# Voeding.net
KiCad netlist of a schematic drawn in Altium Designer
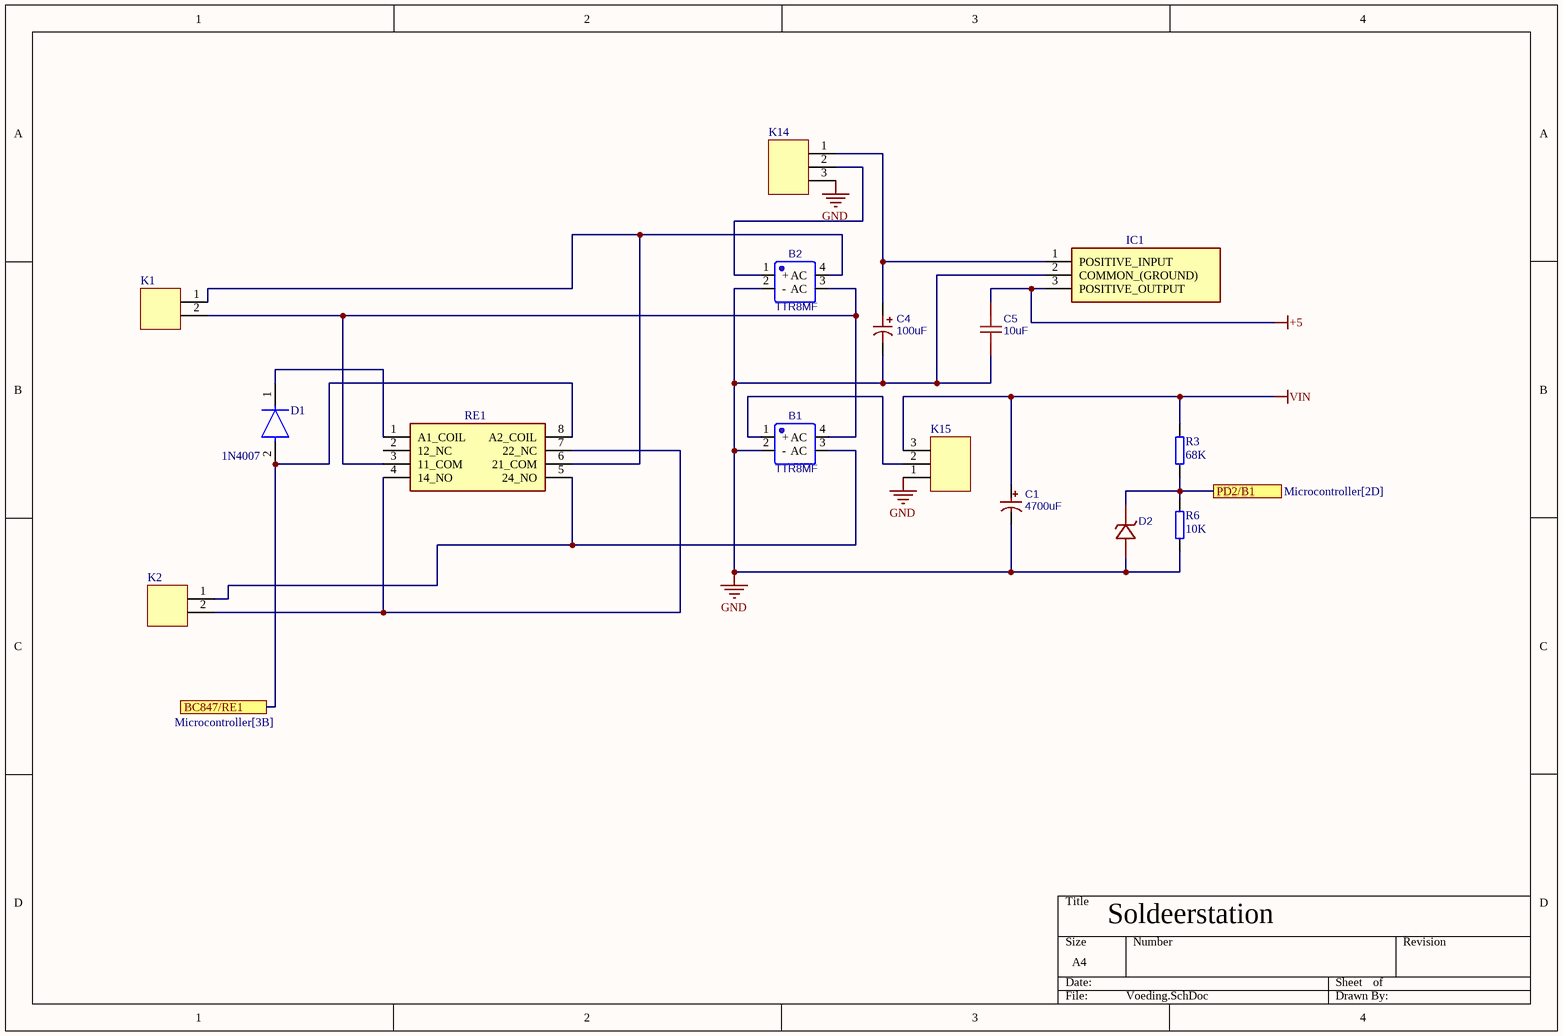
[diagram p0: Voeding.SchDoc]

(export (version "E")
  (design (tool "Eeschema 10.0.6"))
  (components
    (comp (ref "B1")
      (value "TTR8MF")
      (footprint "B1,2 Brug gelijkrichter")
      (fields (field (name "BOM_SUPPLIER PART") "C712546") (field (name "CONTRIBUTOR") "LCSC"))
      (libsource (lib "SoldeerStation") (part "B1,2 Brug Gelijkrichter"))
    )
    (comp (ref "B2")
      (value "TTR8MF")
      (footprint "B1,2 Brug gelijkrichter")
      (fields (field (name "BOM_SUPPLIER PART") "C712546") (field (name "CONTRIBUTOR") "LCSC"))
      (libsource (lib "SoldeerStation") (part "B1,2 Brug Gelijkrichter"))
    )
    (comp (ref "C1")
      (value "4700uF")
      (footprint "C1 4700uF")
      (fields
        (field (name "BOM_MANUFACTURER PART") "KM478M050N35RR0VH2FP0")
        (field (name "BOM_SUPPLIER PART") "C45662")
      )
      (libsource (lib "SoldeerStation") (part "C1 4700uF"))
    )
    (comp (ref "C4")
      (value "100uF")
      (footprint "C4 100uF")
      (fields
        (field (name "BOM_SUPPLIER PART") "C445063")
        (field (name "BOM_MANUFACTURER PART") "UWT1H101MNL1GS")
        (field (name "CONTRIBUTOR") "LCSC")
      )
      (libsource (lib "SoldeerStation") (part "C4 100uF"))
    )
    (comp (ref "C5")
      (value "10uF")
      (footprint "C2,5,10 10uF")
      (fields
        (field (name "BOM_SUPPLIER PART") "C440198")
        (field (name "BOM_MANUFACTURER PART") "GRM21BR61H106KE43L")
        (field (name "CONTRIBUTOR") "LCSC")
      )
      (libsource (lib "SoldeerStation") (part "C2,5,10 10uF"))
    )
    (comp (ref "D1")
      (value "1N4007")
      (footprint "FP-1N4007-MFG")
      (description "DIODE GEN PURP 1KV 1A DO204AL")
      (fields
        (field (name "OCTOPART") "https://octopart.com/1n4007-e3%2F54-vishay-39548207")
        (field (name "MANUFACTURER") "Vishay")
      )
      (libsource (lib "SoldeerStation") (part "zo_1N4007"))
    )
    (comp (ref "D2")
      (value "~")
      (footprint "D2 zener diode")
      (description "BZT52C5V1_C1884555")
      (fields
        (field (name "BOM_SUPPLIER PART") "C1884555")
        (field (name "BOM_MANUFACTURER PART") "BZT52C5V1")
        (field (name "CONTRIBUTOR") "LCSC")
      )
      (libsource (lib "SoldeerStation") (part "D2 zener diode"))
    )
    (comp (ref "IC1")
      (value "~")
      (footprint "IC1 DC-DC converter")
      (description "Non-Isolated DC/DC Converters 7.5W 24Vin 5Vout1 1.5A SIP Non-Iso")
      (fields
        (field (name "MOUSER PART NUMBER") "580-OKI78SR5/1.5W36C")
        (field (name "MANUFACTURER_PART_NUMBER") "OKI-78SR-5/1.5-W36-C")
      )
      (libsource (lib "SoldeerStation") (part "IC1 OKI-78SR-5_1.5-W36-C"))
    )
    (comp (ref "K1")
      (value "~")
      (footprint "Terminal_2")
      (libsource (lib "SoldeerStation") (part "K Terminal_2"))
    )
    (comp (ref "K2")
      (value "~")
      (footprint "Terminal_2")
      (libsource (lib "SoldeerStation") (part "K Terminal_2"))
    )
    (comp (ref "K14")
      (value "~")
      (footprint "PInHeader_3")
      (libsource (lib "SoldeerStation") (part "K PinHeader_3"))
    )
    (comp (ref "K15") (value "~") (footprint "PInHeader_3") (libsource (lib "") (part "K PinHeader_3_1")))
    (comp (ref "R3")
      (value "68K")
      (footprint "RESC2013X50X30ML20T20")
      (fields (field (name "MANUFACTURER") "Vishay Dale") (field (name "PART NUMBER") "CRCW08050000Z0EA"))
      (libsource (lib "SoldeerStation") (part "R Resistor"))
    )
    (comp (ref "R6")
      (value "10K")
      (footprint "RESC2013X50X30ML20T20")
      (fields (field (name "MANUFACTURER") "Vishay Dale") (field (name "PART NUMBER") "CRCW08050000Z0EA"))
      (libsource (lib "SoldeerStation") (part "R Resistor"))
    )
    (comp (ref "RE1")
      (value "~")
      (footprint "RE1 Vermogen relais")
      (description "RT424005F  General Purpose Relays DPDT 8A 5VDC GEN PURPOSE RELAY")
      (fields
        (field (name "MOUSER PART NUMBER") "655-RT424005F")
        (field (name "MANUFACTURER_PART_NUMBER") "RT424005F")
      )
      (libsource (lib "SoldeerStation") (part "RE1 Vermogen relais"))
    )
  )
  (nets
    (net (code "1") (name "+5") (class "Default")
      (node (ref "C5") (pin "2") (pinfunction "2_2") (pintype "passive"))
      (node (ref "IC1") (pin "3") (pinfunction "POSITIVE_OUTPUT_3") (pintype "passive"))
    )
    (net (code "2") (name "/BC847{slash}RE1") (class "Default")
      (node (ref "D1") (pin "2") (pinfunction "A_2") (pintype "passive"))
      (node (ref "RE1") (pin "8") (pinfunction "A2_COIL_8") (pintype "passive"))
    )
    (net (code "3") (name "/PD2{slash}B1") (class "Default")
      (node (ref "D2") (pin "1") (pinfunction "K_1") (pintype "passive"))
      (node (ref "R3") (pin "1") (pinfunction "1_1") (pintype "passive"))
      (node (ref "R6") (pin "2") (pinfunction "2_2") (pintype "passive"))
    )
    (net (code "4") (name "GND") (class "Default")
      (node (ref "B1") (pin "2") (pinfunction "-_2") (pintype "passive"))
      (node (ref "B2") (pin "2") (pinfunction "-_2") (pintype "passive"))
      (node (ref "C1") (pin "2") (pinfunction "2_2") (pintype "passive"))
      (node (ref "C4") (pin "2") (pinfunction "2_2") (pintype "passive"))
      (node (ref "C5") (pin "1") (pinfunction "1_1") (pintype "passive"))
      (node (ref "D2") (pin "2") (pinfunction "A_2") (pintype "passive"))
      (node (ref "IC1") (pin "2") (pinfunction "COMMON_(GROUND)_2") (pintype "passive"))
      (node (ref "K14") (pin "3") (pintype "passive"))
      (node (ref "K15") (pin "1") (pintype "passive"))
      (node (ref "R6") (pin "1") (pinfunction "1_1") (pintype "passive"))
    )
    (net (code "5") (name "Net-(B1-+)") (class "Default")
      (node (ref "B1") (pin "1") (pinfunction "+_1") (pintype "passive"))
      (node (ref "K15") (pin "2") (pintype "passive"))
    )
    (net (code "6") (name "Net-(B2-+)") (class "Default")
      (node (ref "B2") (pin "1") (pinfunction "+_1") (pintype "passive"))
      (node (ref "K14") (pin "2") (pintype "passive"))
    )
    (net (code "7") (name "Net-(D1-C)") (class "Default")
      (node (ref "D1") (pin "1") (pinfunction "C_1") (pintype "passive"))
      (node (ref "RE1") (pin "1") (pinfunction "A1_COIL_1") (pintype "passive"))
    )
    (net (code "8") (name "Net-(IC1-POSITIVE_INPUT)") (class "Default")
      (node (ref "C4") (pin "1") (pinfunction "1_1") (pintype "passive"))
      (node (ref "IC1") (pin "1") (pinfunction "POSITIVE_INPUT_1") (pintype "passive"))
      (node (ref "K14") (pin "1") (pintype "passive"))
    )
    (net (code "9") (name "Net-(RE1-11_COM)") (class "Default")
      (node (ref "B1") (pin "4") (pinfunction "AC_4") (pintype "passive"))
      (node (ref "B2") (pin "3") (pinfunction "AC_3") (pintype "passive"))
      (node (ref "K1") (pin "2") (pintype "passive"))
      (node (ref "RE1") (pin "3") (pinfunction "11_COM_3") (pintype "passive"))
    )
    (net (code "10") (name "Net-(RE1-14_NO)") (class "Default")
      (node (ref "K2") (pin "2") (pintype "passive"))
      (node (ref "RE1") (pin "4") (pinfunction "14_NO_4") (pintype "passive"))
      (node (ref "RE1") (pin "7") (pinfunction "22_NC_7") (pintype "passive"))
    )
    (net (code "11") (name "Net-(RE1-21_COM)") (class "Default")
      (node (ref "B2") (pin "4") (pinfunction "AC_4") (pintype "passive"))
      (node (ref "K1") (pin "1") (pintype "passive"))
      (node (ref "RE1") (pin "6") (pinfunction "21_COM_6") (pintype "passive"))
    )
    (net (code "12") (name "Net-(RE1-24_NO)") (class "Default")
      (node (ref "B1") (pin "3") (pinfunction "AC_3") (pintype "passive"))
      (node (ref "K2") (pin "1") (pintype "passive"))
      (node (ref "RE1") (pin "5") (pinfunction "24_NO_5") (pintype "passive"))
    )
    (net (code "13") (name "VIN") (class "Default")
      (node (ref "C1") (pin "1") (pinfunction "1_1") (pintype "passive"))
      (node (ref "K15") (pin "3") (pintype "passive"))
      (node (ref "R3") (pin "2") (pinfunction "2_2") (pintype "passive"))
    )
    (net (code "14") (name "unconnected-(RE1-12_NC-Pad2)") (class "Default")
      (node (ref "RE1") (pin "2") (pinfunction "12_NC_2") (pintype "passive"))
    )
  )
)
